# Button.net
KiCad netlist of a schematic drawn in Altium Designer
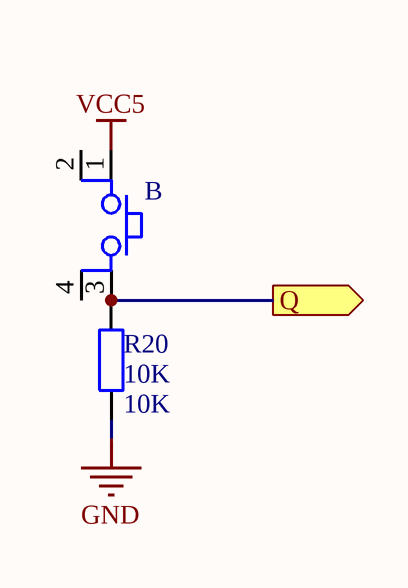
[diagram p0: Button.SchDoc]

(export (version "E")
  (design (tool "Eeschema 10.0.6"))
  (components
    (comp (ref "B")
      (value "~")
      (footprint "FP_BTN_SMD")
      (description "Push button")
      (libsource (lib "hallglib") (part "Button"))
    )
    (comp (ref "R20")
      (value "10K")
      (footprint "FP_0805_RES")
      (description "Resistor")
      (fields
        (field (name "TOLERANCE") "5%")
        (field (name "POWER") "125mW")
        (field (name "ALTIUM_VALUE") "10K")
      )
      (libsource (lib "hallglib") (part "RES 10K"))
    )
  )
  (nets
    (net (code "1") (name "/Q") (class "Default")
      (node (ref "B") (pin "3") (pinfunction "3_3") (pintype "passive"))
      (node (ref "R20") (pin "2") (pinfunction "2_2") (pintype "passive"))
    )
    (net (code "2") (name "GND") (class "Default")
      (node (ref "R20") (pin "1") (pinfunction "1_1") (pintype "passive"))
    )
    (net (code "3") (name "VCC5") (class "Default")
      (node (ref "B") (pin "1") (pinfunction "1_1") (pintype "passive"))
    )
    (net (code "4") (name "unconnected-(B-Pad2)") (class "Default")
      (node (ref "B") (pin "2") (pinfunction "2_2") (pintype "passive"))
    )
    (net (code "5") (name "unconnected-(B-Pad4)") (class "Default")
      (node (ref "B") (pin "4") (pinfunction "4_4") (pintype "passive"))
    )
  )
)
